# Module_4G.net
KiCad netlist of a schematic drawn in Altium Designer
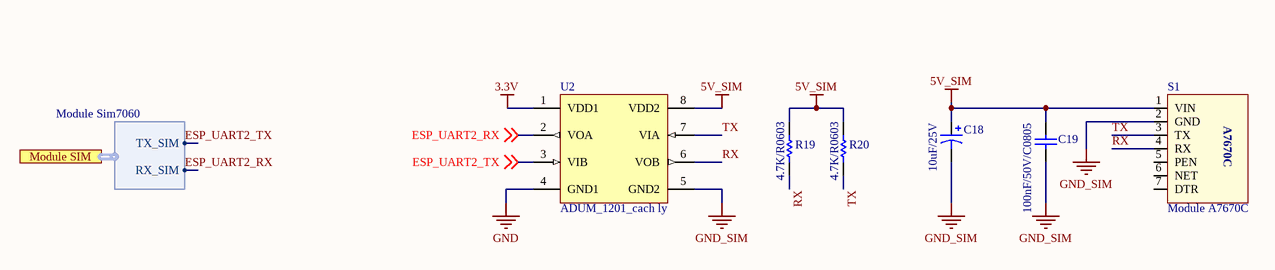
[diagram p0: Module 4G.SchDoc]

(export (version "E")
  (design (tool "Eeschema 10.0.6"))
  (components
    (comp (ref "C18")
      (value "10uF/25V")
      (footprint "Manh_Capacitor:CAP TANT SIZE B")
      (description "CAP TANT 10UF 25V 10% 1411")
      (fields
        (field (name "MANUFACTURER") "KEMET")
        (field (name "MANUFACTURER PART NUMBER") "T491B106K025AT")
      )
      (libsource (lib "Manh_Capacitor") (part "10uF/25V/SIZE B/10%"))
    )
    (comp (ref "C19")
      (value "100nF/50V/C0805")
      (footprint "Manh_Capacitor:C0805")
      (description "CAP CER 0.1UF 50V 10% X7R 0805")
      (fields
        (field (name "MANUFACTURER") "Samsung Electro-Mechanics America, Inc.")
        (field (name "MANUFACTURER PART NUMBER") "CL21B104KBCNNNC")
      )
      (libsource (lib "Manh_Capacitor") (part "0.1uF/50V/C0805/10%"))
    )
    (comp (ref "R19")
      (value "4.7K/R0603")
      (footprint "Manh_Resistor:R0603")
      (description "RES SMD 4.7K OHM 1% 1/10W 0603")
      (fields
        (field (name "MANUFACTURER") "Yageo")
        (field (name "MANUFACTURER PART NUMBER") "RC0603FR-074K7L")
      )
      (libsource (lib "Manh_Resistor") (part "4.7K/R0603/1%"))
    )
    (comp (ref "R20")
      (value "4.7K/R0603")
      (footprint "Manh_Resistor:R0603")
      (description "RES SMD 4.7K OHM 1% 1/10W 0603")
      (fields
        (field (name "MANUFACTURER") "Yageo")
        (field (name "MANUFACTURER PART NUMBER") "RC0603FR-074K7L")
      )
      (libsource (lib "Manh_Resistor") (part "4.7K/R0603/1%"))
    )
    (comp (ref "S1")
      (value "Module A7670C")
      (footprint "Module A7670C")
      (libsource (lib "Nichietsuvn") (part "Module A7670C"))
    )
    (comp (ref "U2")
      (value "ADUM_1201_cach ly")
      (footprint "ADUM1201")
      (libsource (lib "All Library") (part "ADUM_1201_cach ly"))
    )
  )
  (nets
    (net (code "3") (name "/RX") (class "Default")
      (node (ref "R19") (pin "1") (pinfunction "1_1") (pintype "passive"))
      (node (ref "S1") (pin "4") (pinfunction "RX_4") (pintype "passive"))
      (node (ref "U2") (pin "6") (pinfunction "VOB_6") (pintype "output"))
    )
    (net (code "4") (name "/TX") (class "Default")
      (node (ref "R20") (pin "1") (pinfunction "1_1") (pintype "passive"))
      (node (ref "S1") (pin "3") (pinfunction "TX_3") (pintype "passive"))
      (node (ref "U2") (pin "7") (pinfunction "VIA_7") (pintype "input"))
    )
    (net (code "6") (name "3.3V") (class "Default")
      (node (ref "U2") (pin "1") (pinfunction "VDD1_1") (pintype "power_in"))
    )
    (net (code "7") (name "5V_SIM") (class "Default")
      (node (ref "C18") (pin "1") (pinfunction "+_1") (pintype "passive"))
      (node (ref "C19") (pin "2") (pinfunction "2_2") (pintype "passive"))
      (node (ref "R19") (pin "2") (pinfunction "2_2") (pintype "passive"))
      (node (ref "R20") (pin "2") (pinfunction "2_2") (pintype "passive"))
      (node (ref "S1") (pin "1") (pinfunction "VIN_1") (pintype "passive"))
      (node (ref "U2") (pin "8") (pinfunction "VDD2_8") (pintype "power_in"))
    )
    (net (code "8") (name "ESP_UART2_RX") (class "Default")
      (node (ref "U2") (pin "2") (pinfunction "VOA_2") (pintype "output"))
    )
    (net (code "9") (name "ESP_UART2_TX") (class "Default")
      (node (ref "U2") (pin "3") (pinfunction "VIB_3") (pintype "input"))
    )
    (net (code "10") (name "GND") (class "Default")
      (node (ref "U2") (pin "4") (pinfunction "GND1_4") (pintype "power_in"))
    )
    (net (code "11") (name "GND_SIM") (class "Default")
      (node (ref "C18") (pin "2") (pinfunction "-_2") (pintype "passive"))
      (node (ref "C19") (pin "1") (pinfunction "1_1") (pintype "passive"))
      (node (ref "S1") (pin "2") (pinfunction "GND_2") (pintype "passive"))
      (node (ref "U2") (pin "5") (pinfunction "GND2_5") (pintype "power_in"))
    )
    (net (code "12") (name "unconnected-(S1-DTR-Pad7)") (class "Default")
      (node (ref "S1") (pin "7") (pinfunction "DTR_7") (pintype "passive"))
    )
    (net (code "13") (name "unconnected-(S1-NET-Pad6)") (class "Default")
      (node (ref "S1") (pin "6") (pinfunction "NET_6") (pintype "passive"))
    )
    (net (code "14") (name "unconnected-(S1-PEN-Pad5)") (class "Default")
      (node (ref "S1") (pin "5") (pinfunction "PEN_5") (pintype "passive"))
    )
  )
)
